# Navi.net
KiCad netlist of a schematic drawn in EAGLE
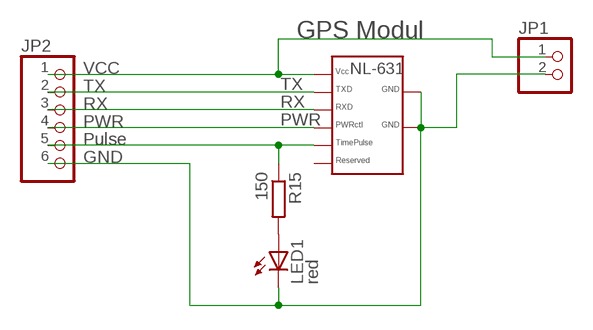
[diagram p0: schematic, sheet 1]

(export (version "E")
  (design (tool "Eeschema 10.0.6"))
  (components
    (comp (ref "JP1")
      (value "PINHD-1X2")
      (footprint "eagle-import:1X02")
      (libsource (lib "eagle-import") (part "PINHD-1X2"))
    )
    (comp (ref "JP2")
      (value "PINHD-1X6")
      (footprint "eagle-import:1X06")
      (libsource (lib "eagle-import") (part "PINHD-1X6"))
    )
    (comp (ref "LED1")
      (value "red")
      (footprint "eagle-import:LED3MM")
      (libsource (lib "eagle-import") (part "LED3MM"))
    )
    (comp (ref "R15")
      (value "150")
      (footprint "eagle-import:R1206")
      (libsource (lib "eagle-import") (part "R-EU_R1206"))
    )
    (comp (ref "U$2")
      (value "NAVILOK-NL-631ETTL")
      (footprint "eagle-import:NAVILOK-NL-631ETTL")
      (libsource (lib "eagle-import") (part "NAVILOK-NL-631ETTL"))
    )
  )
  (nets
    (net (code "1") (name "/PWR") (class "Default")
      (node (ref "JP2") (pin "4") (pinfunction "4_4") (pintype "passive"))
      (node (ref "U$2") (pin "P$4") (pinfunction "P$4_P$4") (pintype "bidirectional"))
    )
    (net (code "2") (name "/RX") (class "Default")
      (node (ref "JP2") (pin "3") (pinfunction "3_3") (pintype "passive"))
      (node (ref "U$2") (pin "P$3") (pinfunction "P$3_P$3") (pintype "bidirectional"))
    )
    (net (code "3") (name "/TX") (class "Default")
      (node (ref "JP2") (pin "2") (pinfunction "2_2") (pintype "passive"))
      (node (ref "U$2") (pin "P$2") (pinfunction "P$2_P$2") (pintype "bidirectional"))
    )
    (net (code "4") (name "Net-(JP1-Pad1)") (class "Default")
      (node (ref "JP1") (pin "1") (pinfunction "1_1") (pintype "passive"))
      (node (ref "JP2") (pin "1") (pinfunction "1_1") (pintype "passive"))
      (node (ref "U$2") (pin "P$1") (pinfunction "P$1_P$1") (pintype "bidirectional"))
    )
    (net (code "5") (name "Net-(JP2-Pad5)") (class "Default")
      (node (ref "JP2") (pin "5") (pinfunction "5_5") (pintype "passive"))
      (node (ref "R15") (pin "1") (pinfunction "1_1") (pintype "passive"))
      (node (ref "U$2") (pin "P$5") (pinfunction "P$5_P$5") (pintype "bidirectional"))
    )
    (net (code "6") (name "Net-(LED1-C)") (class "Default")
      (node (ref "JP1") (pin "2") (pinfunction "2_2") (pintype "passive"))
      (node (ref "JP2") (pin "6") (pinfunction "6_6") (pintype "passive"))
      (node (ref "LED1") (pin "K") (pinfunction "C_K") (pintype "passive"))
      (node (ref "U$2") (pin "P$7") (pinfunction "P$7_P$7") (pintype "bidirectional"))
      (node (ref "U$2") (pin "P$8") (pinfunction "P$8_P$8") (pintype "bidirectional"))
    )
    (net (code "7") (name "Net-(LED1-PadA)") (class "Default")
      (node (ref "LED1") (pin "A") (pinfunction "A_A") (pintype "passive"))
      (node (ref "R15") (pin "2") (pinfunction "2_2") (pintype "passive"))
    )
    (net (code "8") (name "unconnected-(U$2-PadP$6)") (class "Default")
      (node (ref "U$2") (pin "P$6") (pinfunction "P$6_P$6") (pintype "bidirectional"))
    )
  )
)
